# main-wleonardo.net
KiCad netlist of a schematic drawn in EAGLE
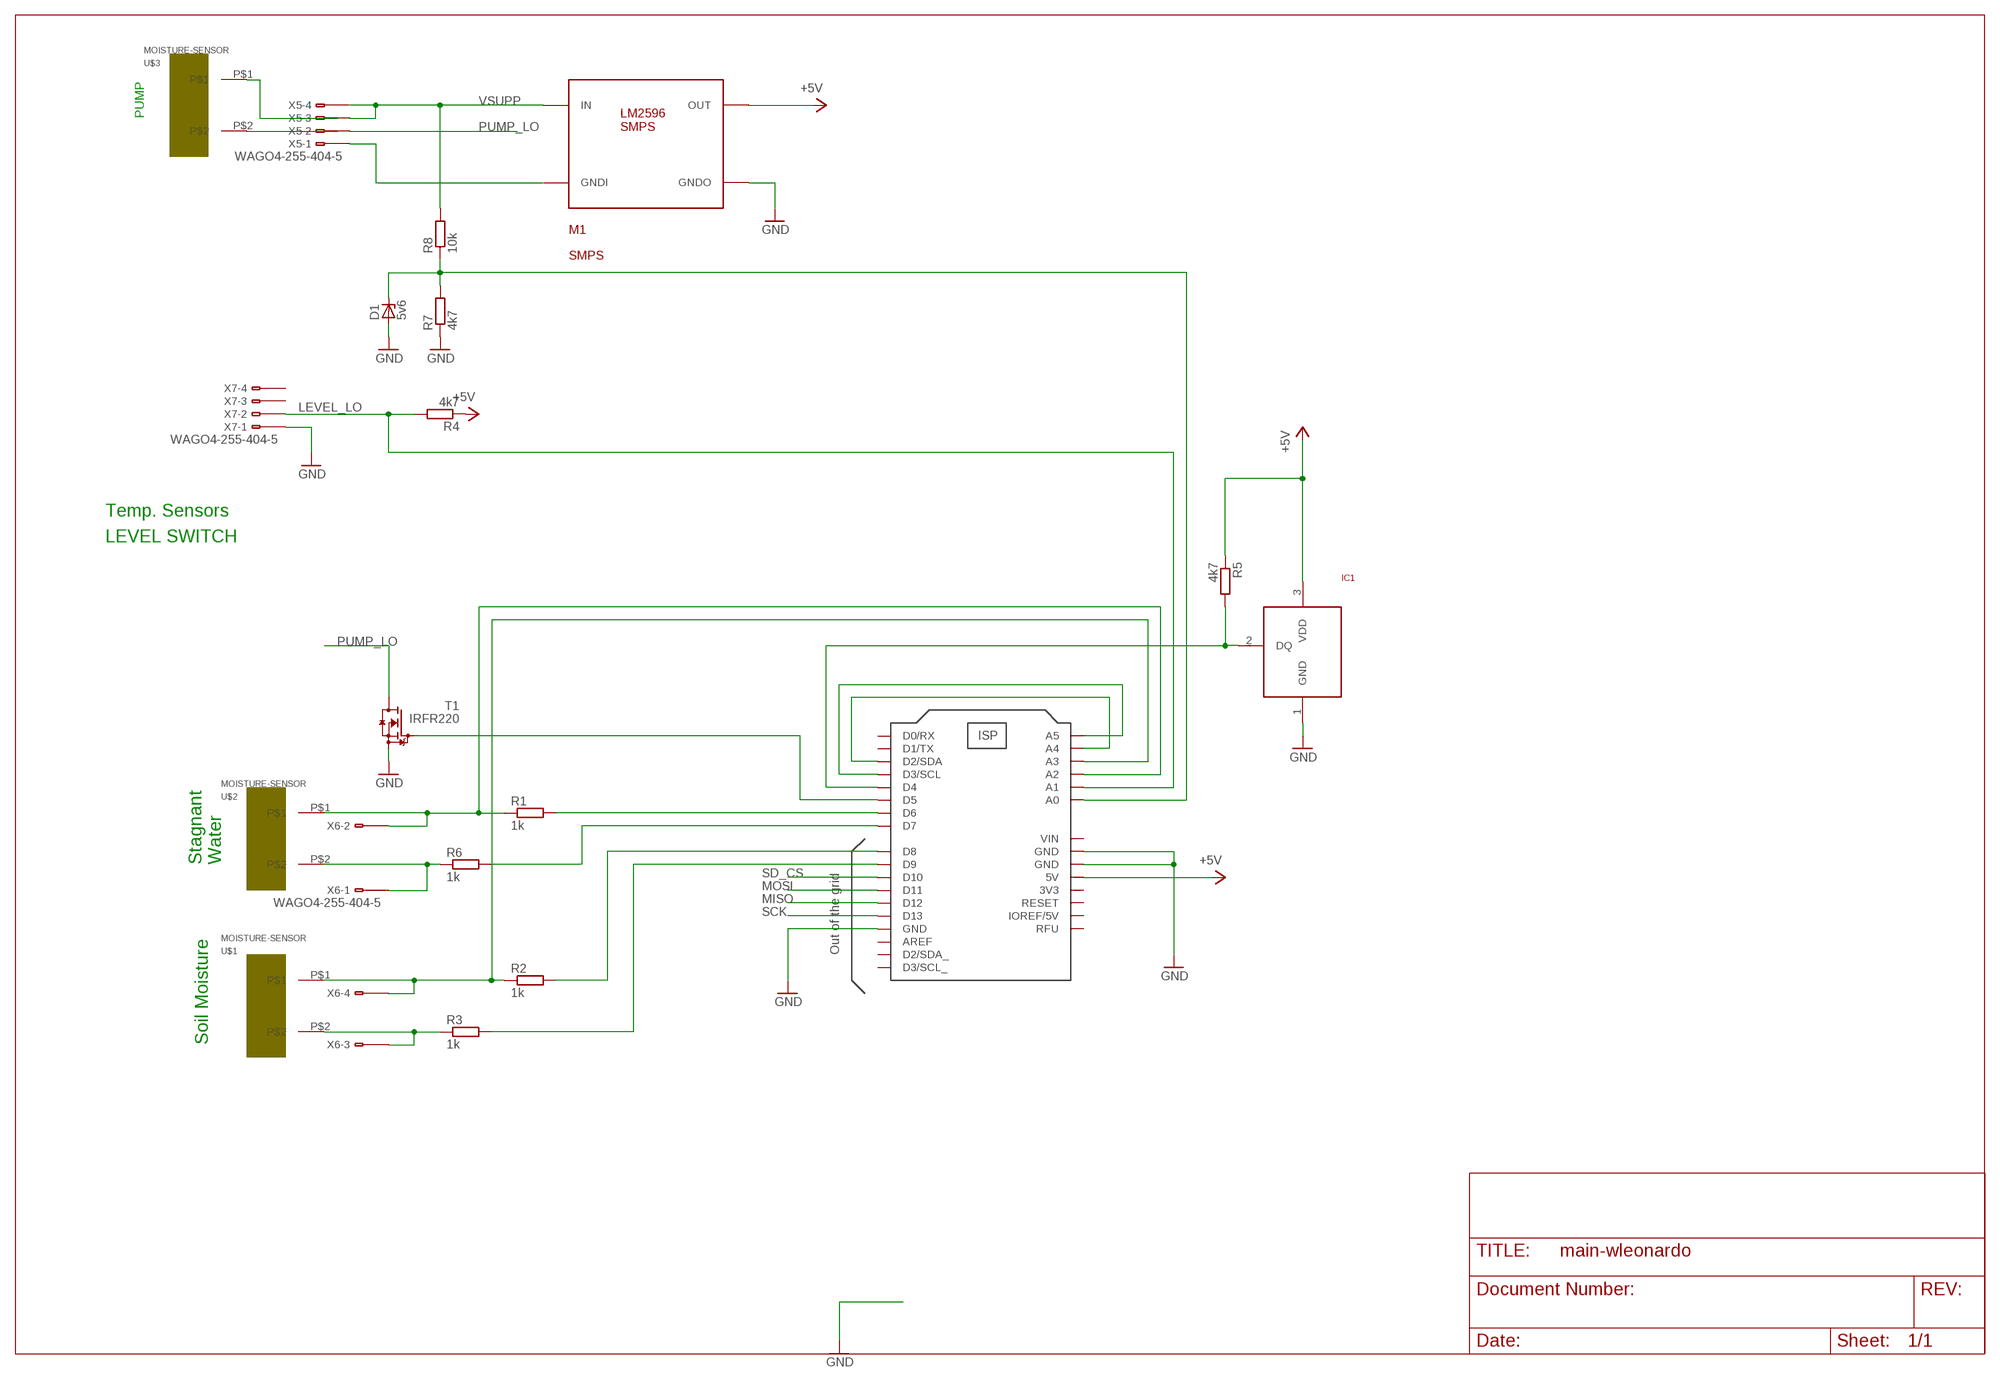
[diagram p0: schematic, sheet 1]

(export (version "E")
  (design (tool "Eeschema 10.0.6"))
  (components
    (comp (ref "D1")
      (value "5v6")
      (footprint "eagle-import:SOT23")
      (libsource (lib "eagle-import") (part "ZENER-DIODESOT23"))
    )
    (comp (ref "IC1")
      (value "PAPP_DS1820")
      (footprint "eagle-import:PAPP_TO92-")
      (libsource (lib "eagle-import") (part "PAPP_DS1820"))
    )
    (comp (ref "LEONARDO")
      (value "SPARKFUN-BOARDS_ARDUINO-LEONARDO-OUTLINE")
      (footprint "eagle-import:SPARKFUN-BOARDS_ARDUINO_R3")
      (libsource (lib "eagle-import") (part "SPARKFUN-BOARDS_ARDUINO-LEONARDO-OUTLINE"))
    )
    (comp (ref "M1")
      (value "SMPS")
      (footprint "eagle-import:SMPS-1")
      (libsource (lib "eagle-import") (part "SMPS"))
    )
    (comp (ref "R1")
      (value "1k")
      (footprint "eagle-import:R0805")
      (libsource (lib "eagle-import") (part "R-EU_R0805"))
    )
    (comp (ref "R2")
      (value "1k")
      (footprint "eagle-import:R0805")
      (libsource (lib "eagle-import") (part "R-EU_R0805"))
    )
    (comp (ref "R3")
      (value "1k")
      (footprint "eagle-import:R0805")
      (libsource (lib "eagle-import") (part "R-EU_R0805"))
    )
    (comp (ref "R4")
      (value "4k7")
      (footprint "eagle-import:R0805")
      (libsource (lib "eagle-import") (part "R-EU_R0805"))
    )
    (comp (ref "R5")
      (value "4k7")
      (footprint "eagle-import:R0805")
      (libsource (lib "eagle-import") (part "R-EU_R0805"))
    )
    (comp (ref "R6")
      (value "1k")
      (footprint "eagle-import:R0805")
      (libsource (lib "eagle-import") (part "R-EU_R0805"))
    )
    (comp (ref "R7")
      (value "4k7")
      (footprint "eagle-import:R0805")
      (libsource (lib "eagle-import") (part "R-EU_R0805"))
    )
    (comp (ref "R8")
      (value "10k")
      (footprint "eagle-import:R0805")
      (libsource (lib "eagle-import") (part "R-EU_R0805"))
    )
    (comp (ref "T1")
      (value "IRFR220")
      (footprint "eagle-import:TO252")
      (libsource (lib "eagle-import") (part "IRFR220"))
    )
    (comp (ref "U$1")
      (value "MOISTURE-SENSOR")
      (footprint "eagle-import:MOISTURE-SENSOR")
      (libsource (lib "eagle-import") (part "MOISTURE-SENSOR"))
    )
    (comp (ref "U$2")
      (value "MOISTURE-SENSOR")
      (footprint "eagle-import:MOISTURE-SENSOR")
      (libsource (lib "eagle-import") (part "MOISTURE-SENSOR"))
    )
    (comp (ref "U$3")
      (value "MOISTURE-SENSOR")
      (footprint "eagle-import:MOISTURE-SENSOR")
      (libsource (lib "eagle-import") (part "MOISTURE-SENSOR"))
    )
    (comp (ref "X5")
      (value "WAGO4-255-404-5")
      (footprint "eagle-import:255-404-5")
      (fields (field (name "MPN") "255-404"))
      (libsource (lib "eagle-import") (part "WAGO4-255-404-5"))
    )
    (comp (ref "X6")
      (value "WAGO4-255-404-5")
      (footprint "eagle-import:255-404-5")
      (fields (field (name "MPN") "255-404"))
      (libsource (lib "eagle-import") (part "WAGO4-255-404-5"))
    )
    (comp (ref "X7")
      (value "WAGO4-255-404-5")
      (footprint "eagle-import:255-404-5")
      (fields (field (name "MPN") "255-404"))
      (libsource (lib "eagle-import") (part "WAGO4-255-404-5"))
    )
  )
  (nets
    (net (code "1") (name "+5V") (class "Default")
      (node (ref "IC1") (pin "3") (pinfunction "VDD_3") (pintype "bidirectional"))
      (node (ref "LEONARDO") (pin "5V") (pinfunction "5V_5V") (pintype "bidirectional"))
      (node (ref "M1") (pin "P$7") (pinfunction "OUT_P$7") (pintype "output"))
      (node (ref "M1") (pin "P$8") (pinfunction "OUT_P$8") (pintype "output"))
      (node (ref "R4") (pin "1") (pinfunction "1_1") (pintype "passive"))
      (node (ref "R5") (pin "1") (pinfunction "1_1") (pintype "passive"))
    )
    (net (code "2") (name "/LEVEL_LO") (class "Default")
      (node (ref "LEONARDO") (pin "A1") (pinfunction "A1_A1") (pintype "bidirectional"))
      (node (ref "R4") (pin "2") (pinfunction "2_2") (pintype "passive"))
      (node (ref "X7") (pin "B2") (pinfunction "B1_B2") (pintype "passive"))
    )
    (net (code "3") (name "/MISO") (class "Default")
      (node (ref "LEONARDO") (pin "D12") (pinfunction "D12_D12") (pintype "bidirectional"))
    )
    (net (code "4") (name "/MOSI") (class "Default")
      (node (ref "LEONARDO") (pin "D11") (pinfunction "D11_D11") (pintype "bidirectional"))
    )
    (net (code "5") (name "/PUMP_LO") (class "Default")
      (node (ref "T1") (pin "3") (pinfunction "D_3") (pintype "passive"))
      (node (ref "X5") (pin "B2") (pinfunction "B1_B2") (pintype "passive"))
    )
    (net (code "6") (name "/SCK") (class "Default")
      (node (ref "LEONARDO") (pin "D13") (pinfunction "D13_D13") (pintype "bidirectional"))
    )
    (net (code "7") (name "/SD_CS") (class "Default")
      (node (ref "LEONARDO") (pin "D10") (pinfunction "D10_D10") (pintype "bidirectional"))
    )
    (net (code "8") (name "/VSUPP") (class "Default")
      (node (ref "M1") (pin "P$3") (pinfunction "IN_P$3") (pintype "input"))
      (node (ref "M1") (pin "P$4") (pinfunction "IN_P$4") (pintype "input"))
      (node (ref "R8") (pin "2") (pinfunction "2_2") (pintype "passive"))
      (node (ref "X5") (pin "B3") (pinfunction "B1_B3") (pintype "passive"))
      (node (ref "X5") (pin "B4") (pinfunction "B1_B4") (pintype "passive"))
    )
    (net (code "9") (name "GND") (class "Default")
      (node (ref "D1") (pin "1") (pinfunction "A_1") (pintype "passive"))
      (node (ref "IC1") (pin "1") (pinfunction "GND_1") (pintype "bidirectional"))
      (node (ref "LEONARDO") (pin "GND@1") (pinfunction "GND_GND@1") (pintype "bidirectional"))
      (node (ref "LEONARDO") (pin "GND@2") (pinfunction "GND_GND@2") (pintype "bidirectional"))
      (node (ref "LEONARDO") (pin "GND@3") (pinfunction "GND_GND@3") (pintype "bidirectional"))
      (node (ref "M1") (pin "P$5") (pinfunction "GNDO_P$5") (pintype "output"))
      (node (ref "M1") (pin "P$6") (pinfunction "GNDO_P$6") (pintype "output"))
      (node (ref "R7") (pin "1") (pinfunction "1_1") (pintype "passive"))
      (node (ref "T1") (pin "2") (pinfunction "S_2") (pintype "passive"))
      (node (ref "X7") (pin "B1") (pinfunction "B1_B1") (pintype "passive"))
    )
    (net (code "10") (name "Net-(D1-C)") (class "Default")
      (node (ref "D1") (pin "3") (pinfunction "C_3") (pintype "passive"))
      (node (ref "LEONARDO") (pin "A0") (pinfunction "A0_A0") (pintype "bidirectional"))
      (node (ref "R7") (pin "2") (pinfunction "2_2") (pintype "passive"))
      (node (ref "R8") (pin "1") (pinfunction "1_1") (pintype "passive"))
    )
    (net (code "11") (name "Net-(IC1-DQ)") (class "Default")
      (node (ref "IC1") (pin "2") (pinfunction "DQ_2") (pintype "bidirectional"))
      (node (ref "LEONARDO") (pin "D4") (pinfunction "D4_D4") (pintype "bidirectional"))
      (node (ref "R5") (pin "2") (pinfunction "2_2") (pintype "passive"))
    )
    (net (code "12") (name "Net-(LEONARDO-D2{slash}SDA)") (class "Default")
      (node (ref "LEONARDO") (pin "A4") (pinfunction "A4_A4") (pintype "bidirectional"))
      (node (ref "LEONARDO") (pin "D2") (pinfunction "D2/SDA_D2") (pintype "bidirectional"))
    )
    (net (code "13") (name "Net-(LEONARDO-D3{slash}SCL)") (class "Default")
      (node (ref "LEONARDO") (pin "A5") (pinfunction "A5_A5") (pintype "bidirectional"))
      (node (ref "LEONARDO") (pin "D3") (pinfunction "D3/SCL_D3") (pintype "bidirectional"))
    )
    (net (code "14") (name "Net-(LEONARDO-PadD6)") (class "Default")
      (node (ref "LEONARDO") (pin "D6") (pinfunction "D6_D6") (pintype "bidirectional"))
      (node (ref "R1") (pin "2") (pinfunction "2_2") (pintype "passive"))
    )
    (net (code "15") (name "Net-(LEONARDO-PadD7)") (class "Default")
      (node (ref "LEONARDO") (pin "D7") (pinfunction "D7_D7") (pintype "bidirectional"))
      (node (ref "R6") (pin "2") (pinfunction "2_2") (pintype "passive"))
    )
    (net (code "16") (name "Net-(LEONARDO-PadD8)") (class "Default")
      (node (ref "LEONARDO") (pin "D8") (pinfunction "D8_D8") (pintype "bidirectional"))
      (node (ref "R2") (pin "2") (pinfunction "2_2") (pintype "passive"))
    )
    (net (code "17") (name "Net-(LEONARDO-PadD9)") (class "Default")
      (node (ref "LEONARDO") (pin "D9") (pinfunction "D9_D9") (pintype "bidirectional"))
      (node (ref "R3") (pin "2") (pinfunction "2_2") (pintype "passive"))
    )
    (net (code "18") (name "Net-(M1-GNDI-PadP$1)") (class "Default")
      (node (ref "M1") (pin "P$1") (pinfunction "GNDI_P$1") (pintype "input"))
      (node (ref "M1") (pin "P$2") (pinfunction "GNDI_P$2") (pintype "input"))
      (node (ref "X5") (pin "B1") (pinfunction "B1_B1") (pintype "passive"))
    )
    (net (code "19") (name "Net-(R6-Pad1)") (class "Default")
      (node (ref "R6") (pin "1") (pinfunction "1_1") (pintype "passive"))
      (node (ref "U$2") (pin "P$2") (pinfunction "P$2_P$2") (pintype "bidirectional"))
      (node (ref "X6") (pin "B1") (pinfunction "B1_B1") (pintype "passive"))
    )
    (net (code "20") (name "Net-(T1-G)") (class "Default")
      (node (ref "LEONARDO") (pin "D5") (pinfunction "D5_D5") (pintype "bidirectional"))
      (node (ref "T1") (pin "1") (pinfunction "G_1") (pintype "passive"))
    )
    (net (code "21") (name "Net-(X5B-A1)") (class "Default")
      (node (ref "U$3") (pin "P$2") (pinfunction "P$2_P$2") (pintype "bidirectional"))
      (node (ref "X5") (pin "A2") (pinfunction "A1_A2") (pintype "passive"))
    )
    (net (code "22") (name "Net-(X5C-A1)") (class "Default")
      (node (ref "U$3") (pin "P$1") (pinfunction "P$1_P$1") (pintype "bidirectional"))
      (node (ref "X5") (pin "A3") (pinfunction "A1_A3") (pintype "passive"))
    )
    (net (code "23") (name "Net-(X6B-B1)") (class "Default")
      (node (ref "LEONARDO") (pin "A2") (pinfunction "A2_A2") (pintype "bidirectional"))
      (node (ref "R1") (pin "1") (pinfunction "1_1") (pintype "passive"))
      (node (ref "U$2") (pin "P$1") (pinfunction "P$1_P$1") (pintype "bidirectional"))
      (node (ref "X6") (pin "B2") (pinfunction "B1_B2") (pintype "passive"))
    )
    (net (code "24") (name "Net-(X6C-B1)") (class "Default")
      (node (ref "R3") (pin "1") (pinfunction "1_1") (pintype "passive"))
      (node (ref "U$1") (pin "P$2") (pinfunction "P$2_P$2") (pintype "bidirectional"))
      (node (ref "X6") (pin "B3") (pinfunction "B1_B3") (pintype "passive"))
    )
    (net (code "25") (name "Net-(X6D-B1)") (class "Default")
      (node (ref "LEONARDO") (pin "A3") (pinfunction "A3_A3") (pintype "bidirectional"))
      (node (ref "R2") (pin "1") (pinfunction "1_1") (pintype "passive"))
      (node (ref "U$1") (pin "P$1") (pinfunction "P$1_P$1") (pintype "bidirectional"))
      (node (ref "X6") (pin "B4") (pinfunction "B1_B4") (pintype "passive"))
    )
    (net (code "26") (name "unconnected-(LEONARDO-3V3-Pad3.3V)") (class "Default")
      (node (ref "LEONARDO") (pin "3.3V") (pinfunction "3V3_3.3V") (pintype "bidirectional"))
    )
    (net (code "27") (name "unconnected-(LEONARDO-D0{slash}RX-PadD0)") (class "Default")
      (node (ref "LEONARDO") (pin "D0") (pinfunction "D0/RX_D0") (pintype "bidirectional"))
    )
    (net (code "28") (name "unconnected-(LEONARDO-D1{slash}TX-PadD1)") (class "Default")
      (node (ref "LEONARDO") (pin "D1") (pinfunction "D1/TX_D1") (pintype "bidirectional"))
    )
    (net (code "29") (name "unconnected-(LEONARDO-D2{slash}SDA_-PadSDA)") (class "Default")
      (node (ref "LEONARDO") (pin "SDA") (pinfunction "D2/SDA__SDA") (pintype "bidirectional"))
    )
    (net (code "30") (name "unconnected-(LEONARDO-D3{slash}SCL_-PadSCL)") (class "Default")
      (node (ref "LEONARDO") (pin "SCL") (pinfunction "D3/SCL__SCL") (pintype "bidirectional"))
    )
    (net (code "31") (name "unconnected-(LEONARDO-IOREF{slash}5V-PadIOREF)") (class "Default")
      (node (ref "LEONARDO") (pin "IOREF") (pinfunction "IOREF/5V_IOREF") (pintype "bidirectional"))
    )
    (net (code "32") (name "unconnected-(LEONARDO-PadAREF)") (class "Default")
      (node (ref "LEONARDO") (pin "AREF") (pinfunction "AREF_AREF") (pintype "bidirectional"))
    )
    (net (code "33") (name "unconnected-(LEONARDO-PadVIN)") (class "Default")
      (node (ref "LEONARDO") (pin "VIN") (pinfunction "VIN_VIN") (pintype "bidirectional"))
    )
    (net (code "34") (name "unconnected-(LEONARDO-RESET-PadRESET@1)") (class "Default")
      (node (ref "LEONARDO") (pin "RESET@1") (pinfunction "RESET_RESET@1") (pintype "bidirectional"))
    )
    (net (code "35") (name "unconnected-(LEONARDO-RFU-PadGND@4)") (class "Default")
      (node (ref "LEONARDO") (pin "GND@4") (pinfunction "RFU_GND@4") (pintype "no_connect"))
    )
    (net (code "36") (name "unconnected-(X5-PadA1)") (class "Default")
      (node (ref "X5") (pin "A1") (pinfunction "A1_A1") (pintype "passive"))
    )
    (net (code "37") (name "unconnected-(X5D-A1-PadA4)") (class "Default")
      (node (ref "X5") (pin "A4") (pinfunction "A1_A4") (pintype "passive"))
    )
    (net (code "38") (name "unconnected-(X6-PadA1)") (class "Default")
      (node (ref "X6") (pin "A1") (pinfunction "A1_A1") (pintype "passive"))
    )
    (net (code "39") (name "unconnected-(X6B-A1-PadA2)") (class "Default")
      (node (ref "X6") (pin "A2") (pinfunction "A1_A2") (pintype "passive"))
    )
    (net (code "40") (name "unconnected-(X6C-A1-PadA3)") (class "Default")
      (node (ref "X6") (pin "A3") (pinfunction "A1_A3") (pintype "passive"))
    )
    (net (code "41") (name "unconnected-(X6D-A1-PadA4)") (class "Default")
      (node (ref "X6") (pin "A4") (pinfunction "A1_A4") (pintype "passive"))
    )
    (net (code "42") (name "unconnected-(X7-PadA1)") (class "Default")
      (node (ref "X7") (pin "A1") (pinfunction "A1_A1") (pintype "passive"))
    )
    (net (code "43") (name "unconnected-(X7B-A1-PadA2)") (class "Default")
      (node (ref "X7") (pin "A2") (pinfunction "A1_A2") (pintype "passive"))
    )
    (net (code "44") (name "unconnected-(X7C-A1-PadA3)") (class "Default")
      (node (ref "X7") (pin "A3") (pinfunction "A1_A3") (pintype "passive"))
    )
    (net (code "45") (name "unconnected-(X7C-B1-PadB3)") (class "Default")
      (node (ref "X7") (pin "B3") (pinfunction "B1_B3") (pintype "passive"))
    )
    (net (code "46") (name "unconnected-(X7D-A1-PadA4)") (class "Default")
      (node (ref "X7") (pin "A4") (pinfunction "A1_A4") (pintype "passive"))
    )
    (net (code "47") (name "unconnected-(X7D-B1-PadB4)") (class "Default")
      (node (ref "X7") (pin "B4") (pinfunction "B1_B4") (pintype "passive"))
    )
  )
)
